# layout.net
KiCad netlist of a schematic drawn in EAGLE
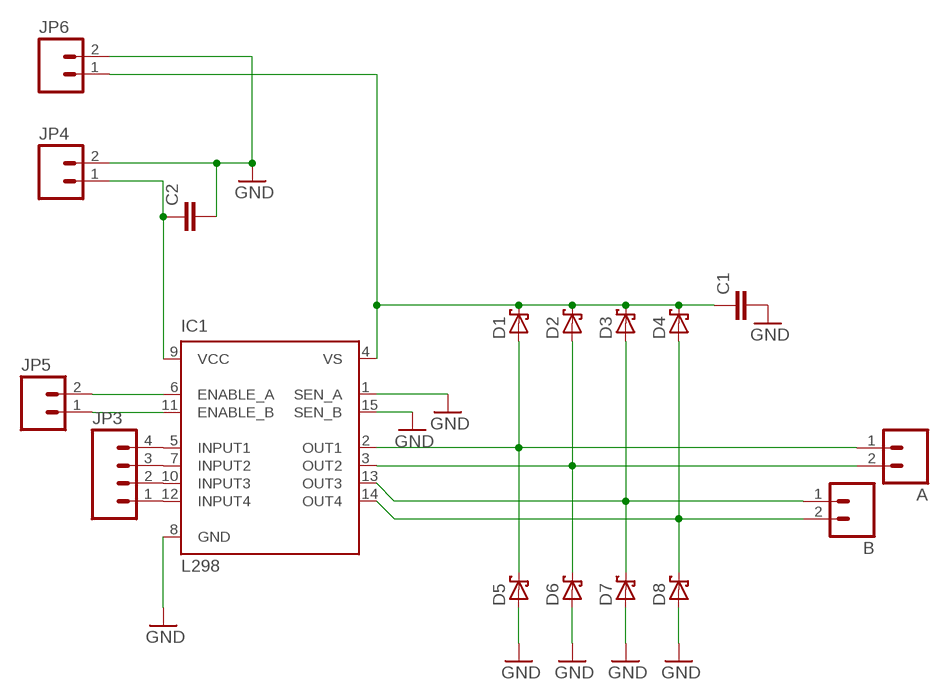
[diagram p0: schematic, sheet 1]

(export (version "E")
  (design (tool "Eeschema 10.0.6"))
  (components
    (comp (ref "A")
      (value "M02PTH4")
      (footprint "eagle-import:1X02_XTRA_BIG")
      (libsource (lib "eagle-import") (part "M02PTH4"))
    )
    (comp (ref "B")
      (value "M02PTH4")
      (footprint "eagle-import:1X02_XTRA_BIG")
      (libsource (lib "eagle-import") (part "M02PTH4"))
    )
    (comp (ref "C1")
      (value "C2,5-3")
      (footprint "eagle-import:C2.5-3")
      (libsource (lib "eagle-import") (part "C2,5-3"))
    )
    (comp (ref "C2")
      (value "C2,5-3")
      (footprint "eagle-import:C2.5-3")
      (libsource (lib "eagle-import") (part "C2,5-3"))
    )
    (comp (ref "D1")
      (value "SCHOTTKY-DIODEF126Z12")
      (footprint "eagle-import:F126Z12")
      (libsource (lib "eagle-import") (part "SCHOTTKY-DIODEF126Z12"))
    )
    (comp (ref "D2")
      (value "SCHOTTKY-DIODEF126Z12")
      (footprint "eagle-import:F126Z12")
      (libsource (lib "eagle-import") (part "SCHOTTKY-DIODEF126Z12"))
    )
    (comp (ref "D3")
      (value "SCHOTTKY-DIODEF126Z12")
      (footprint "eagle-import:F126Z12")
      (libsource (lib "eagle-import") (part "SCHOTTKY-DIODEF126Z12"))
    )
    (comp (ref "D4")
      (value "SCHOTTKY-DIODEF126Z12")
      (footprint "eagle-import:F126Z12")
      (libsource (lib "eagle-import") (part "SCHOTTKY-DIODEF126Z12"))
    )
    (comp (ref "D5")
      (value "SCHOTTKY-DIODEF126Z12")
      (footprint "eagle-import:F126Z12")
      (libsource (lib "eagle-import") (part "SCHOTTKY-DIODEF126Z12"))
    )
    (comp (ref "D6")
      (value "SCHOTTKY-DIODEF126Z12")
      (footprint "eagle-import:F126Z12")
      (libsource (lib "eagle-import") (part "SCHOTTKY-DIODEF126Z12"))
    )
    (comp (ref "D7")
      (value "SCHOTTKY-DIODEF126Z12")
      (footprint "eagle-import:F126Z12")
      (libsource (lib "eagle-import") (part "SCHOTTKY-DIODEF126Z12"))
    )
    (comp (ref "D8")
      (value "SCHOTTKY-DIODEF126Z12")
      (footprint "eagle-import:F126Z12")
      (libsource (lib "eagle-import") (part "SCHOTTKY-DIODEF126Z12"))
    )
    (comp (ref "IC1")
      (value "L298")
      (footprint "eagle-import:MULTIWATT-15")
      (fields (field (name "MPN") "L298N"))
      (libsource (lib "eagle-import") (part "L298"))
    )
    (comp (ref "JP3")
      (value "M04POLAR")
      (footprint "eagle-import:MOLEX-1X4")
      (libsource (lib "eagle-import") (part "M04POLAR"))
    )
    (comp (ref "JP4")
      (value "M021X02_NO_SILK")
      (footprint "eagle-import:1X02_NO_SILK")
      (libsource (lib "eagle-import") (part "M021X02_NO_SILK"))
    )
    (comp (ref "JP5")
      (value "M02PTH")
      (footprint "eagle-import:1X02")
      (libsource (lib "eagle-import") (part "M02PTH"))
    )
    (comp (ref "JP6")
      (value "M021X02_NO_SILK")
      (footprint "eagle-import:1X02_NO_SILK")
      (libsource (lib "eagle-import") (part "M021X02_NO_SILK"))
    )
  )
  (nets
    (net (code "1") (name "GND") (class "Default")
      (node (ref "C1") (pin "2") (pinfunction "2_2") (pintype "passive"))
      (node (ref "C2") (pin "2") (pinfunction "2_2") (pintype "passive"))
      (node (ref "D5") (pin "A") (pinfunction "A_A") (pintype "passive"))
      (node (ref "D6") (pin "A") (pinfunction "A_A") (pintype "passive"))
      (node (ref "D7") (pin "A") (pinfunction "A_A") (pintype "passive"))
      (node (ref "D8") (pin "A") (pinfunction "A_A") (pintype "passive"))
      (node (ref "IC1") (pin "1") (pinfunction "SEN_A_1") (pintype "input"))
      (node (ref "IC1") (pin "15") (pinfunction "SEN_B_15") (pintype "input"))
      (node (ref "IC1") (pin "8") (pinfunction "GND_8") (pintype "power_in"))
      (node (ref "JP4") (pin "2") (pinfunction "2_2") (pintype "passive"))
      (node (ref "JP6") (pin "2") (pinfunction "2_2") (pintype "passive"))
    )
    (net (code "2") (name "Net-(IC1-ENABLE_A)") (class "Default")
      (node (ref "IC1") (pin "6") (pinfunction "ENABLE_A_6") (pintype "input"))
      (node (ref "JP5") (pin "2") (pinfunction "2_2") (pintype "passive"))
    )
    (net (code "3") (name "Net-(IC1-ENABLE_B)") (class "Default")
      (node (ref "IC1") (pin "11") (pinfunction "ENABLE_B_11") (pintype "input"))
      (node (ref "JP5") (pin "1") (pinfunction "1_1") (pintype "passive"))
    )
    (net (code "4") (name "Net-(IC1-INPUT1)") (class "Default")
      (node (ref "IC1") (pin "5") (pinfunction "INPUT1_5") (pintype "input"))
      (node (ref "JP3") (pin "4") (pinfunction "4_4") (pintype "passive"))
    )
    (net (code "5") (name "Net-(IC1-INPUT2)") (class "Default")
      (node (ref "IC1") (pin "7") (pinfunction "INPUT2_7") (pintype "input"))
      (node (ref "JP3") (pin "3") (pinfunction "3_3") (pintype "passive"))
    )
    (net (code "6") (name "Net-(IC1-INPUT3)") (class "Default")
      (node (ref "IC1") (pin "10") (pinfunction "INPUT3_10") (pintype "input"))
      (node (ref "JP3") (pin "2") (pinfunction "2_2") (pintype "passive"))
    )
    (net (code "7") (name "Net-(IC1-INPUT4)") (class "Default")
      (node (ref "IC1") (pin "12") (pinfunction "INPUT4_12") (pintype "input"))
      (node (ref "JP3") (pin "1") (pinfunction "1_1") (pintype "passive"))
    )
    (net (code "8") (name "Net-(IC1-OUT1)") (class "Default")
      (node (ref "A") (pin "1") (pinfunction "1_1") (pintype "passive"))
      (node (ref "D1") (pin "A") (pinfunction "A_A") (pintype "passive"))
      (node (ref "D5") (pin "C") (pinfunction "C_C") (pintype "passive"))
      (node (ref "IC1") (pin "2") (pinfunction "OUT1_2") (pintype "output"))
    )
    (net (code "9") (name "Net-(IC1-OUT2)") (class "Default")
      (node (ref "A") (pin "2") (pinfunction "2_2") (pintype "passive"))
      (node (ref "D2") (pin "A") (pinfunction "A_A") (pintype "passive"))
      (node (ref "D6") (pin "C") (pinfunction "C_C") (pintype "passive"))
      (node (ref "IC1") (pin "3") (pinfunction "OUT2_3") (pintype "output"))
    )
    (net (code "10") (name "Net-(IC1-OUT3)") (class "Default")
      (node (ref "B") (pin "1") (pinfunction "1_1") (pintype "passive"))
      (node (ref "D3") (pin "A") (pinfunction "A_A") (pintype "passive"))
      (node (ref "D7") (pin "C") (pinfunction "C_C") (pintype "passive"))
      (node (ref "IC1") (pin "13") (pinfunction "OUT3_13") (pintype "output"))
    )
    (net (code "11") (name "Net-(IC1-OUT4)") (class "Default")
      (node (ref "B") (pin "2") (pinfunction "2_2") (pintype "passive"))
      (node (ref "D4") (pin "A") (pinfunction "A_A") (pintype "passive"))
      (node (ref "D8") (pin "C") (pinfunction "C_C") (pintype "passive"))
      (node (ref "IC1") (pin "14") (pinfunction "OUT4_14") (pintype "output"))
    )
    (net (code "12") (name "Net-(IC1-VCC)") (class "Default")
      (node (ref "C2") (pin "1") (pinfunction "1_1") (pintype "passive"))
      (node (ref "IC1") (pin "9") (pinfunction "VCC_9") (pintype "power_in"))
      (node (ref "JP4") (pin "1") (pinfunction "1_1") (pintype "passive"))
    )
    (net (code "13") (name "Net-(IC1-VS)") (class "Default")
      (node (ref "C1") (pin "1") (pinfunction "1_1") (pintype "passive"))
      (node (ref "D1") (pin "C") (pinfunction "C_C") (pintype "passive"))
      (node (ref "D2") (pin "C") (pinfunction "C_C") (pintype "passive"))
      (node (ref "D3") (pin "C") (pinfunction "C_C") (pintype "passive"))
      (node (ref "D4") (pin "C") (pinfunction "C_C") (pintype "passive"))
      (node (ref "IC1") (pin "4") (pinfunction "VS_4") (pintype "power_in"))
      (node (ref "JP6") (pin "1") (pinfunction "1_1") (pintype "passive"))
    )
  )
)
